# fat41p.net
KiCad netlist of a schematic drawn in Altium Designer
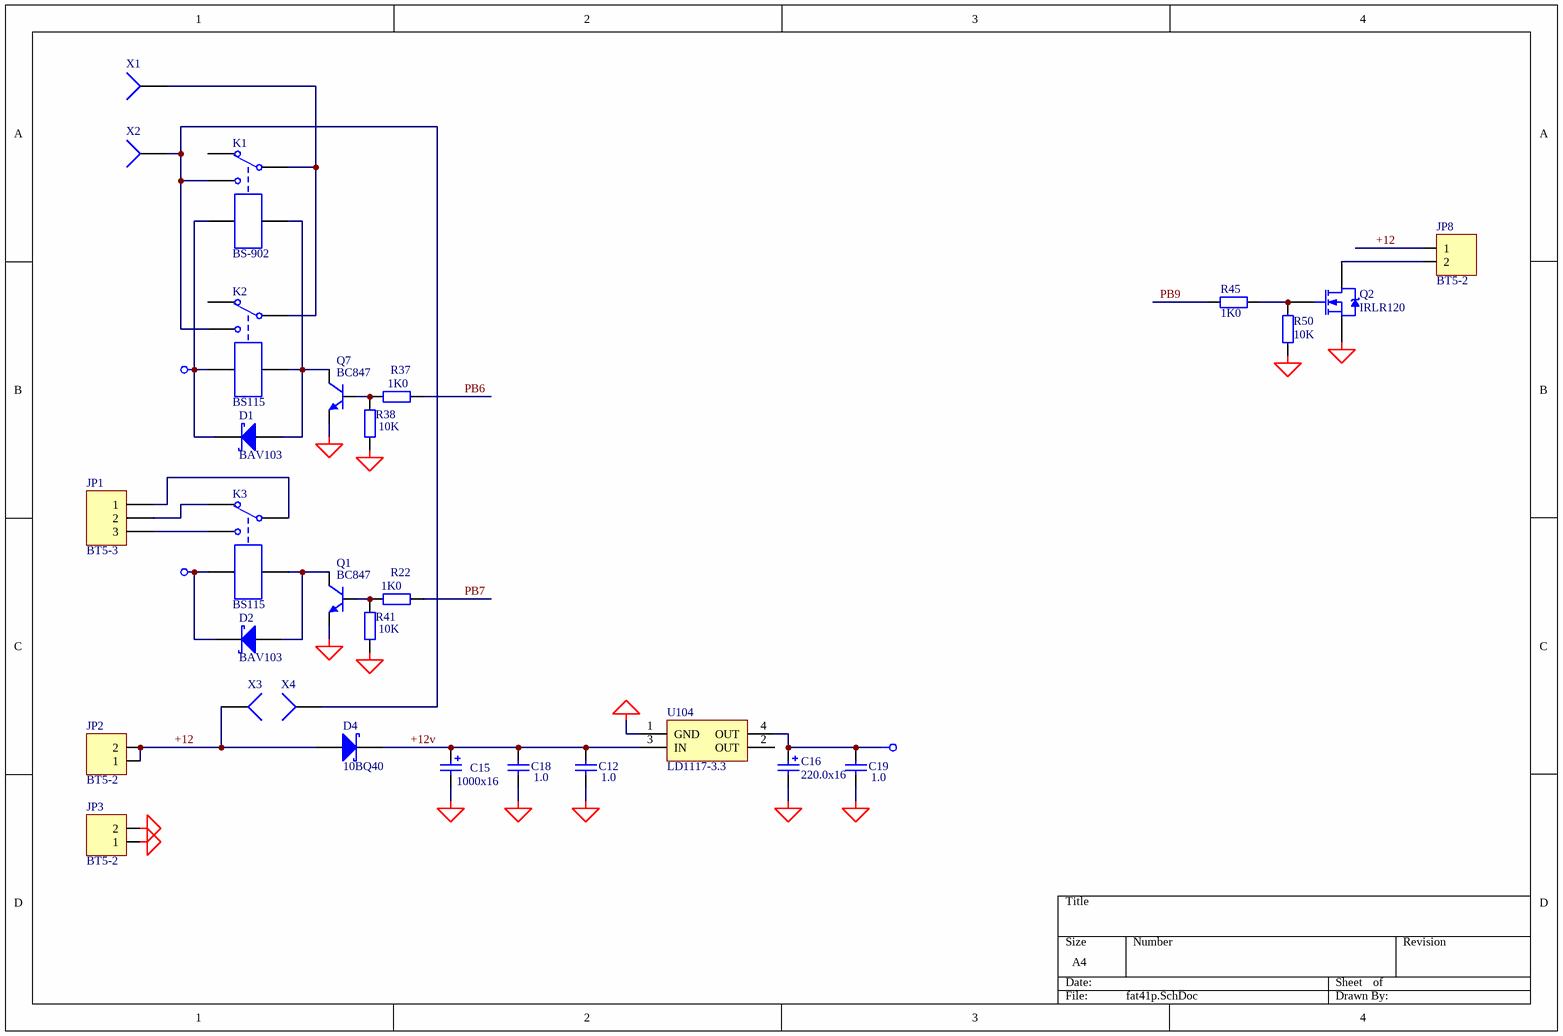
[diagram p0: fat41p.SchDoc]

(export (version "E")
  (design (tool "Eeschema 10.0.6"))
  (components
    (comp (ref "C12")
      (value "1.0")
      (footprint "_1206")
      (description "Capacitor")
      (fields (field (name "MANUFACTURER") "Generic Components") (field (name "PUBLISHER") "Altium Limited"))
      (libsource (lib "BUF") (part "Cap"))
    )
    (comp (ref "C15")
      (value "1000x16")
      (footprint "el5")
      (description "Polarized Capacitor (Radial)")
      (fields (field (name "MANUFACTURER") "Generic Components") (field (name "PUBLISHER") "Altium Limited"))
      (libsource (lib "BUF") (part "Cap Pol1"))
    )
    (comp (ref "C16")
      (value "220.0x16")
      (footprint "el3")
      (description "Polarized Capacitor (Radial)")
      (fields (field (name "MANUFACTURER") "Generic Components") (field (name "PUBLISHER") "Altium Limited"))
      (libsource (lib "BUF") (part "Cap Pol"))
    )
    (comp (ref "C18")
      (value "1.0")
      (footprint "_1206")
      (description "Capacitor")
      (fields (field (name "MANUFACTURER") "Generic Components") (field (name "PUBLISHER") "Altium Limited"))
      (libsource (lib "BUF") (part "Cap"))
    )
    (comp (ref "C19")
      (value "1.0")
      (footprint "_1206")
      (description "Capacitor")
      (fields (field (name "MANUFACTURER") "Generic Components") (field (name "PUBLISHER") "Altium Limited"))
      (libsource (lib "BUF") (part "Cap"))
    )
    (comp (ref "D1")
      (value "BAV103")
      (footprint "_1206d")
      (description "Schottky Rectifier")
      (fields
        (field (name "MANUFACTURER") "International Rectifier")
        (field (name "PUBLISHER") "Altium Limited")
      )
      (libsource (lib "IR Discrete Diode") (part "10BQ015"))
    )
    (comp (ref "D2")
      (value "BAV103")
      (footprint "_1206d")
      (description "Schottky Rectifier")
      (fields
        (field (name "MANUFACTURER") "International Rectifier")
        (field (name "PUBLISHER") "Altium Limited")
      )
      (libsource (lib "IR Discrete Diode") (part "10BQ015"))
    )
    (comp (ref "D4")
      (value "10BQ40")
      (footprint "DSO-C2/X2.3")
      (description "Schottky Rectifier")
      (fields
        (field (name "MANUFACTURER") "International Rectifier")
        (field (name "PUBLISHER") "Altium Limited")
      )
      (libsource (lib "IR Discrete Diode") (part "10BQ015"))
    )
    (comp (ref "JP1")
      (value "BT5-3")
      (footprint "BT5-3")
      (description "Header, 3-Pin")
      (fields (field (name "MANUFACTURER") "Generic Components") (field (name "PUBLISHER") "Altium Limited"))
      (libsource (lib "Miscellaneous Connectors") (part "Header 3"))
    )
    (comp (ref "JP2")
      (value "BT5-2")
      (footprint "BT5-2-1")
      (description "Header, 3-Pin")
      (fields (field (name "MANUFACTURER") "Generic Components") (field (name "PUBLISHER") "Altium Limited"))
      (libsource (lib "") (part "BT5-2_1"))
    )
    (comp (ref "JP3")
      (value "BT5-2")
      (footprint "BT5-2-1")
      (description "Header, 3-Pin")
      (fields (field (name "MANUFACTURER") "Generic Components") (field (name "PUBLISHER") "Altium Limited"))
      (libsource (lib "") (part "BT5-2_1"))
    )
    (comp (ref "JP8")
      (value "BT5-2")
      (footprint "BT5-2-1")
      (description "Header, 3-Pin")
      (fields (field (name "MANUFACTURER") "Generic Components") (field (name "PUBLISHER") "Altium Limited"))
      (libsource (lib "PAL") (part "BT5-2"))
    )
    (comp (ref "K1")
      (value "BS-902")
      (footprint "BS-902")
      (description "Single-Pole Dual-Throw Relay")
      (fields (field (name "MANUFACTURER") "Generic Components") (field (name "PUBLISHER") "Altium Limited"))
      (libsource (lib "PAL") (part "BS115"))
    )
    (comp (ref "K2")
      (value "BS115")
      (footprint "BS115")
      (description "Single-Pole Dual-Throw Relay")
      (fields (field (name "MANUFACTURER") "Generic Components") (field (name "PUBLISHER") "Altium Limited"))
      (libsource (lib "PAL") (part "BS115"))
    )
    (comp (ref "K3")
      (value "BS115")
      (footprint "BS115")
      (description "Single-Pole Dual-Throw Relay")
      (fields (field (name "MANUFACTURER") "Generic Components") (field (name "PUBLISHER") "Altium Limited"))
      (libsource (lib "PAL") (part "BS115"))
    )
    (comp (ref "Q1")
      (value "BC847")
      (footprint "SO-G3")
      (description "General Purpose Transistor NPN Silicon")
      (fields (field (name "MANUFACTURER") "Motorola") (field (name "PUBLISHER") "Altium Limited"))
      (libsource (lib "PAL") (part "BC847ALT1"))
    )
    (comp (ref "Q2")
      (value "IRLR120")
      (footprint "SIP-G3/E8")
      (description "HEXFET N-Channel Power MOSFET")
      (fields
        (field (name "MANUFACTURER") "International Rectifier")
        (field (name "PUBLISHER") "Altium Limited")
      )
      (libsource (lib "IR Discrete MOSFET") (part "IRFR120"))
    )
    (comp (ref "Q7")
      (value "BC847")
      (footprint "SO-G3")
      (description "General Purpose Transistor NPN Silicon")
      (fields (field (name "MANUFACTURER") "Motorola") (field (name "PUBLISHER") "Altium Limited"))
      (libsource (lib "PAL") (part "BC847ALT1"))
    )
    (comp (ref "R22")
      (value "1K0")
      (footprint "_1206")
      (description "Resistor")
      (fields (field (name "MANUFACTURER") "Generic Components") (field (name "PUBLISHER") "Altium Limited"))
      (libsource (lib "Miscellaneous Devices") (part "Res2"))
    )
    (comp (ref "R37")
      (value "1K0")
      (footprint "_1206")
      (description "Resistor")
      (fields (field (name "MANUFACTURER") "Generic Components") (field (name "PUBLISHER") "Altium Limited"))
      (libsource (lib "Miscellaneous Devices") (part "Res2"))
    )
    (comp (ref "R38")
      (value "10K")
      (footprint "_1206")
      (description "Resistor")
      (fields (field (name "MANUFACTURER") "Generic Components") (field (name "PUBLISHER") "Altium Limited"))
      (libsource (lib "") (part "Res2_1"))
    )
    (comp (ref "R41")
      (value "10K")
      (footprint "_1206")
      (description "Resistor")
      (fields (field (name "MANUFACTURER") "Generic Components") (field (name "PUBLISHER") "Altium Limited"))
      (libsource (lib "") (part "Res2_1"))
    )
    (comp (ref "R45")
      (value "1K0")
      (footprint "_1206")
      (description "Resistor")
      (fields (field (name "MANUFACTURER") "Generic Components") (field (name "PUBLISHER") "Altium Limited"))
      (libsource (lib "Miscellaneous Devices") (part "Res2"))
    )
    (comp (ref "R50")
      (value "10K")
      (footprint "_1206")
      (description "Resistor")
      (fields (field (name "MANUFACTURER") "Generic Components") (field (name "PUBLISHER") "Altium Limited"))
      (libsource (lib "") (part "Res2_1"))
    )
    (comp (ref "U104")
      (value "LD1117-3.3")
      (footprint "SIP-G3/C7.4")
      (description "800mA and 1A Low Dropout Positive Regulator 2.85V, 3.3V, 5V, and Adjustable")
      (fields (field (name "MANUFACTURER") "Burr-Brown") (field (name "PUBLISHER") "Altium Limited"))
      (libsource (lib "BB Power Mgt Voltage Regulator") (part "REG1117-3.3"))
    )
    (comp (ref "X1")
      (value "~")
      (footprint "PAL:PIN3")
      (description "Socket")
      (fields (field (name "MANUFACTURER") "Generic Components") (field (name "PUBLISHER") "Altium Limited"))
      (libsource (lib "Miscellaneous Connectors") (part "Socket"))
    )
    (comp (ref "X2")
      (value "~")
      (footprint "PAL:PIN3")
      (description "Socket")
      (fields (field (name "MANUFACTURER") "Generic Components") (field (name "PUBLISHER") "Altium Limited"))
      (libsource (lib "Miscellaneous Connectors") (part "Socket"))
    )
    (comp (ref "X3")
      (value "~")
      (footprint "PIN1")
      (description "Socket")
      (fields (field (name "MANUFACTURER") "Generic Components") (field (name "PUBLISHER") "Altium Limited"))
      (libsource (lib "Miscellaneous Connectors") (part "Socket"))
    )
    (comp (ref "X4")
      (value "~")
      (footprint "PIN1")
      (description "Socket")
      (fields (field (name "MANUFACTURER") "Generic Components") (field (name "PUBLISHER") "Altium Limited"))
      (libsource (lib "Miscellaneous Connectors") (part "Socket"))
    )
  )
  (nets
    (net (code "1") (name "+3v3") (class "Default")
      (node (ref "C16") (pin "1") (pinfunction "1_1") (pintype "passive"))
      (node (ref "C19") (pin "2") (pinfunction "2_2") (pintype "passive"))
      (node (ref "U104") (pin "4") (pinfunction "OUT_4") (pintype "power_in"))
    )
    (net (code "2") (name "+12v") (class "Default")
      (node (ref "C12") (pin "2") (pinfunction "2_2") (pintype "passive"))
      (node (ref "C15") (pin "1") (pinfunction "1_1") (pintype "passive"))
      (node (ref "C18") (pin "2") (pinfunction "2_2") (pintype "passive"))
      (node (ref "D1") (pin "2") (pinfunction "K_2") (pintype "passive"))
      (node (ref "D2") (pin "2") (pinfunction "K_2") (pintype "passive"))
      (node (ref "D4") (pin "2") (pinfunction "K_2") (pintype "passive"))
      (node (ref "K1") (pin "5") (pinfunction "5_5") (pintype "passive"))
      (node (ref "K2") (pin "5") (pinfunction "5_5") (pintype "passive"))
      (node (ref "K3") (pin "5") (pinfunction "5_5") (pintype "passive"))
      (node (ref "U104") (pin "3") (pinfunction "IN_3") (pintype "power_in"))
    )
    (net (code "3") (name "/+12") (class "Default")
      (node (ref "D4") (pin "1") (pinfunction "A_1") (pintype "passive"))
      (node (ref "JP2") (pin "1") (pinfunction "1_1") (pintype "passive"))
      (node (ref "JP2") (pin "2") (pinfunction "2_2") (pintype "passive"))
      (node (ref "JP8") (pin "1") (pinfunction "1_1") (pintype "passive"))
      (node (ref "X3") (pin "1") (pinfunction "1_1") (pintype "passive"))
    )
    (net (code "4") (name "/PB6") (class "Default")
      (node (ref "R37") (pin "2") (pinfunction "2_2") (pintype "passive"))
    )
    (net (code "5") (name "/PB7") (class "Default")
      (node (ref "R22") (pin "2") (pinfunction "2_2") (pintype "passive"))
    )
    (net (code "6") (name "/PB9") (class "Default")
      (node (ref "R45") (pin "1") (pinfunction "1_1") (pintype "passive"))
    )
    (net (code "7") (name "GND") (class "Default")
      (node (ref "C12") (pin "1") (pinfunction "1_1") (pintype "passive"))
      (node (ref "C15") (pin "2") (pinfunction "2_2") (pintype "passive"))
      (node (ref "C16") (pin "2") (pinfunction "2_2") (pintype "passive"))
      (node (ref "C18") (pin "1") (pinfunction "1_1") (pintype "passive"))
      (node (ref "C19") (pin "1") (pinfunction "1_1") (pintype "passive"))
      (node (ref "JP3") (pin "1") (pinfunction "1_1") (pintype "passive"))
      (node (ref "JP3") (pin "2") (pinfunction "2_2") (pintype "passive"))
      (node (ref "Q1") (pin "2") (pinfunction "E_2") (pintype "passive"))
      (node (ref "Q2") (pin "3") (pinfunction "S_3") (pintype "passive"))
      (node (ref "Q7") (pin "2") (pinfunction "E_2") (pintype "passive"))
      (node (ref "R38") (pin "2") (pinfunction "2_2") (pintype "passive"))
      (node (ref "R41") (pin "2") (pinfunction "2_2") (pintype "passive"))
      (node (ref "R50") (pin "2") (pinfunction "2_2") (pintype "passive"))
      (node (ref "U104") (pin "1") (pinfunction "GND_1") (pintype "power_in"))
    )
    (net (code "8") (name "Net-(D1-A)") (class "Default")
      (node (ref "D1") (pin "1") (pinfunction "A_1") (pintype "passive"))
      (node (ref "K1") (pin "4") (pinfunction "4_4") (pintype "passive"))
      (node (ref "K2") (pin "4") (pinfunction "4_4") (pintype "passive"))
      (node (ref "Q7") (pin "3") (pinfunction "C_3") (pintype "passive"))
    )
    (net (code "9") (name "Net-(D2-A)") (class "Default")
      (node (ref "D2") (pin "1") (pinfunction "A_1") (pintype "passive"))
      (node (ref "K3") (pin "4") (pinfunction "4_4") (pintype "passive"))
      (node (ref "Q1") (pin "3") (pinfunction "C_3") (pintype "passive"))
    )
    (net (code "10") (name "Net-(JP1-Pad1)") (class "Default")
      (node (ref "JP1") (pin "1") (pinfunction "1_1") (pintype "passive"))
      (node (ref "K3") (pin "1") (pinfunction "1_1") (pintype "passive"))
    )
    (net (code "11") (name "Net-(JP1-Pad2)") (class "Default")
      (node (ref "JP1") (pin "2") (pinfunction "2_2") (pintype "passive"))
      (node (ref "K3") (pin "2") (pinfunction "2_2") (pintype "passive"))
    )
    (net (code "12") (name "Net-(JP1-Pad3)") (class "Default")
      (node (ref "JP1") (pin "3") (pinfunction "3_3") (pintype "passive"))
      (node (ref "K3") (pin "3") (pinfunction "3_3") (pintype "passive"))
    )
    (net (code "13") (name "Net-(K1-Pad1)") (class "Default")
      (node (ref "K1") (pin "1") (pinfunction "1_1") (pintype "passive"))
      (node (ref "K2") (pin "1") (pinfunction "1_1") (pintype "passive"))
      (node (ref "X1") (pin "1") (pinfunction "1_1") (pintype "passive"))
    )
    (net (code "14") (name "Net-(K1-Pad3)") (class "Default")
      (node (ref "K1") (pin "3") (pinfunction "3_3") (pintype "passive"))
      (node (ref "K2") (pin "3") (pinfunction "3_3") (pintype "passive"))
      (node (ref "X2") (pin "1") (pinfunction "1_1") (pintype "passive"))
      (node (ref "X4") (pin "1") (pinfunction "1_1") (pintype "passive"))
    )
    (net (code "15") (name "Net-(Q1-B)") (class "Default")
      (node (ref "Q1") (pin "1") (pinfunction "B_1") (pintype "passive"))
      (node (ref "R22") (pin "1") (pinfunction "1_1") (pintype "passive"))
      (node (ref "R41") (pin "1") (pinfunction "1_1") (pintype "passive"))
    )
    (net (code "16") (name "Net-(Q2-D)") (class "Default")
      (node (ref "JP8") (pin "2") (pinfunction "2_2") (pintype "passive"))
      (node (ref "Q2") (pin "4") (pinfunction "D_4") (pintype "passive"))
    )
    (net (code "17") (name "Net-(Q2-G)") (class "Default")
      (node (ref "Q2") (pin "1") (pinfunction "G_1") (pintype "passive"))
      (node (ref "R45") (pin "2") (pinfunction "2_2") (pintype "passive"))
      (node (ref "R50") (pin "1") (pinfunction "1_1") (pintype "passive"))
    )
    (net (code "18") (name "Net-(Q7-B)") (class "Default")
      (node (ref "Q7") (pin "1") (pinfunction "B_1") (pintype "passive"))
      (node (ref "R37") (pin "1") (pinfunction "1_1") (pintype "passive"))
      (node (ref "R38") (pin "1") (pinfunction "1_1") (pintype "passive"))
    )
    (net (code "19") (name "unconnected-(K1-Pad2)") (class "Default")
      (node (ref "K1") (pin "2") (pinfunction "2_2") (pintype "passive"))
    )
    (net (code "20") (name "unconnected-(K2-Pad2)") (class "Default")
      (node (ref "K2") (pin "2") (pinfunction "2_2") (pintype "passive"))
    )
    (net (code "21") (name "unconnected-(U104-OUT-Pad2)") (class "Default")
      (node (ref "U104") (pin "2") (pinfunction "OUT_2") (pintype "power_in"))
    )
  )
)
